# IN-17_tubes.net
KiCad netlist of a schematic drawn in EAGLE
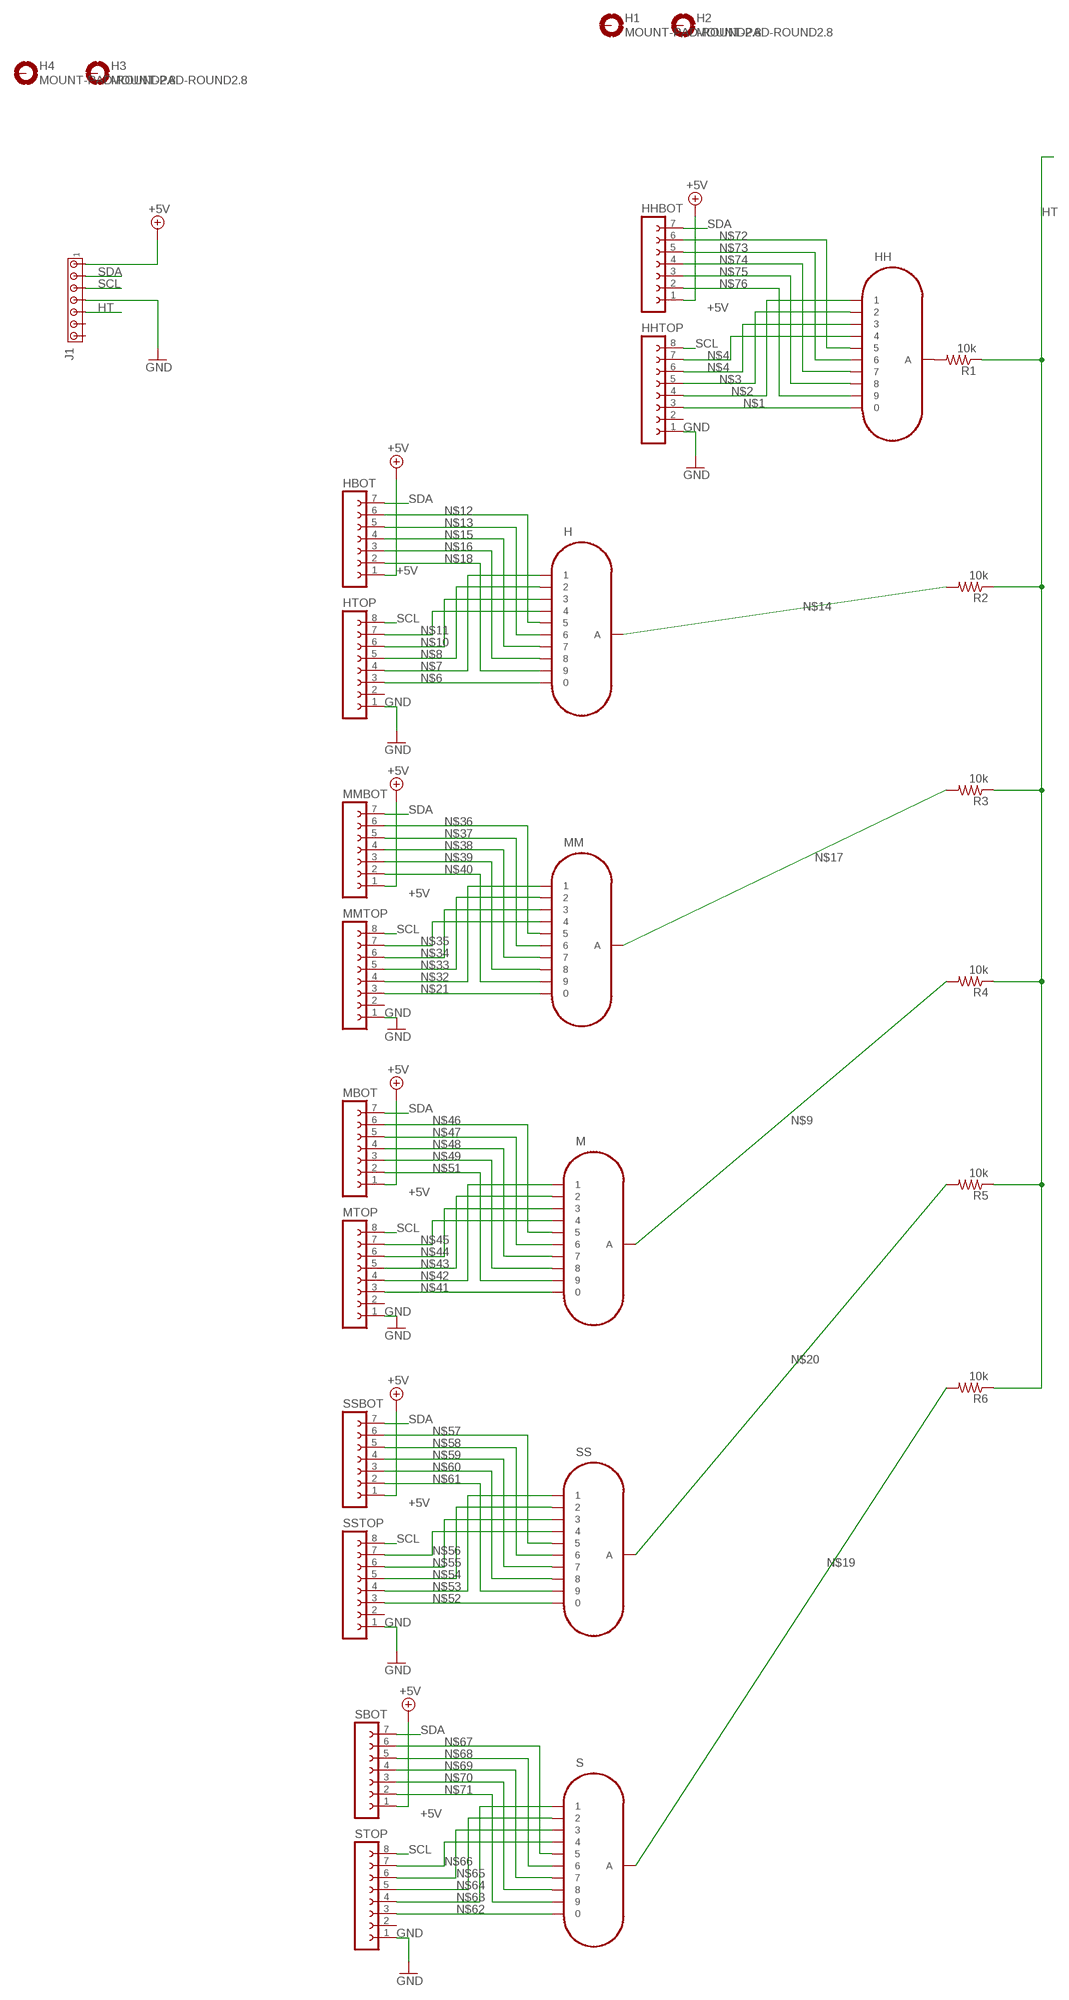
[diagram p0: schematic, sheet 1]

(export (version "E")
  (design (tool "Eeschema 10.0.6"))
  (components
    (comp (ref "H")
      (value "IN-17")
      (footprint "eagle-import:IN-17")
      (libsource (lib "eagle-import") (part "IN-17"))
    )
    (comp (ref "H1")
      (value "MOUNT-PAD-ROUND2.8")
      (footprint "eagle-import:2,8-PAD")
      (libsource (lib "eagle-import") (part "MOUNT-PAD-ROUND2.8"))
    )
    (comp (ref "H2")
      (value "MOUNT-PAD-ROUND2.8")
      (footprint "eagle-import:2,8-PAD")
      (libsource (lib "eagle-import") (part "MOUNT-PAD-ROUND2.8"))
    )
    (comp (ref "H3")
      (value "MOUNT-PAD-ROUND2.8")
      (footprint "eagle-import:2,8-PAD")
      (libsource (lib "eagle-import") (part "MOUNT-PAD-ROUND2.8"))
    )
    (comp (ref "H4")
      (value "MOUNT-PAD-ROUND2.8")
      (footprint "eagle-import:2,8-PAD")
      (libsource (lib "eagle-import") (part "MOUNT-PAD-ROUND2.8"))
    )
    (comp (ref "HBOT")
      (value "FE07-1")
      (footprint "eagle-import:FE07")
      (libsource (lib "eagle-import") (part "FE07-1"))
    )
    (comp (ref "HH")
      (value "IN-17")
      (footprint "eagle-import:IN-17")
      (libsource (lib "eagle-import") (part "IN-17"))
    )
    (comp (ref "HHBOT")
      (value "FE07-1")
      (footprint "eagle-import:FE07")
      (libsource (lib "eagle-import") (part "FE07-1"))
    )
    (comp (ref "HHTOP")
      (value "FE08-1")
      (footprint "eagle-import:FE08")
      (libsource (lib "eagle-import") (part "FE08-1"))
    )
    (comp (ref "HTOP")
      (value "FE08-1")
      (footprint "eagle-import:FE08")
      (libsource (lib "eagle-import") (part "FE08-1"))
    )
    (comp (ref "J1")
      (value "MTA07-100")
      (footprint "eagle-import:10X07MTA")
      (libsource (lib "eagle-import") (part "MTA07-100"))
    )
    (comp (ref "M")
      (value "IN-17")
      (footprint "eagle-import:IN-17")
      (libsource (lib "eagle-import") (part "IN-17"))
    )
    (comp (ref "MBOT")
      (value "FE07-1")
      (footprint "eagle-import:FE07")
      (libsource (lib "eagle-import") (part "FE07-1"))
    )
    (comp (ref "MM")
      (value "IN-17")
      (footprint "eagle-import:IN-17")
      (libsource (lib "eagle-import") (part "IN-17"))
    )
    (comp (ref "MMBOT")
      (value "FE07-1")
      (footprint "eagle-import:FE07")
      (libsource (lib "eagle-import") (part "FE07-1"))
    )
    (comp (ref "MMTOP")
      (value "FE08-1")
      (footprint "eagle-import:FE08")
      (libsource (lib "eagle-import") (part "FE08-1"))
    )
    (comp (ref "MTOP")
      (value "FE08-1")
      (footprint "eagle-import:FE08")
      (libsource (lib "eagle-import") (part "FE08-1"))
    )
    (comp (ref "R1")
      (value "10k")
      (footprint "eagle-import:M0805")
      (libsource (lib "eagle-import") (part "R-US_M0805"))
    )
    (comp (ref "R2")
      (value "10k")
      (footprint "eagle-import:M0805")
      (libsource (lib "eagle-import") (part "R-US_M0805"))
    )
    (comp (ref "R3")
      (value "10k")
      (footprint "eagle-import:M0805")
      (libsource (lib "eagle-import") (part "R-US_M0805"))
    )
    (comp (ref "R4")
      (value "10k")
      (footprint "eagle-import:M0805")
      (libsource (lib "eagle-import") (part "R-US_M0805"))
    )
    (comp (ref "R5")
      (value "10k")
      (footprint "eagle-import:M0805")
      (libsource (lib "eagle-import") (part "R-US_M0805"))
    )
    (comp (ref "R6")
      (value "10k")
      (footprint "eagle-import:M0805")
      (libsource (lib "eagle-import") (part "R-US_M0805"))
    )
    (comp (ref "S")
      (value "IN-17")
      (footprint "eagle-import:IN-17")
      (libsource (lib "eagle-import") (part "IN-17"))
    )
    (comp (ref "SBOT")
      (value "FE07-1")
      (footprint "eagle-import:FE07")
      (libsource (lib "eagle-import") (part "FE07-1"))
    )
    (comp (ref "SS")
      (value "IN-17")
      (footprint "eagle-import:IN-17")
      (libsource (lib "eagle-import") (part "IN-17"))
    )
    (comp (ref "SSBOT")
      (value "FE07-1")
      (footprint "eagle-import:FE07")
      (libsource (lib "eagle-import") (part "FE07-1"))
    )
    (comp (ref "SSTOP")
      (value "FE08-1")
      (footprint "eagle-import:FE08")
      (libsource (lib "eagle-import") (part "FE08-1"))
    )
    (comp (ref "STOP")
      (value "FE08-1")
      (footprint "eagle-import:FE08")
      (libsource (lib "eagle-import") (part "FE08-1"))
    )
  )
  (nets
    (net (code "1") (name "+5V") (class "Default")
      (node (ref "HBOT") (pin "1") (pinfunction "1_1") (pintype "passive"))
      (node (ref "HHBOT") (pin "1") (pinfunction "1_1") (pintype "passive"))
      (node (ref "J1") (pin "1") (pinfunction "1_1") (pintype "passive"))
      (node (ref "MBOT") (pin "1") (pinfunction "1_1") (pintype "passive"))
      (node (ref "MMBOT") (pin "1") (pinfunction "1_1") (pintype "passive"))
      (node (ref "SBOT") (pin "1") (pinfunction "1_1") (pintype "passive"))
      (node (ref "SSBOT") (pin "1") (pinfunction "1_1") (pintype "passive"))
    )
    (net (code "2") (name "/HT") (class "Default")
      (node (ref "J1") (pin "5") (pinfunction "5_5") (pintype "passive"))
      (node (ref "R1") (pin "1") (pinfunction "1_1") (pintype "passive"))
      (node (ref "R2") (pin "1") (pinfunction "1_1") (pintype "passive"))
      (node (ref "R3") (pin "1") (pinfunction "1_1") (pintype "passive"))
      (node (ref "R4") (pin "1") (pinfunction "1_1") (pintype "passive"))
      (node (ref "R5") (pin "1") (pinfunction "1_1") (pintype "passive"))
      (node (ref "R6") (pin "1") (pinfunction "1_1") (pintype "passive"))
    )
    (net (code "3") (name "/N$1") (class "Default")
      (node (ref "HH") (pin "0") (pinfunction "0_0") (pintype "bidirectional"))
      (node (ref "HHTOP") (pin "3") (pinfunction "3_3") (pintype "passive"))
    )
    (net (code "4") (name "/N$2") (class "Default")
      (node (ref "HH") (pin "1") (pinfunction "1_1") (pintype "bidirectional"))
      (node (ref "HHTOP") (pin "4") (pinfunction "4_4") (pintype "passive"))
    )
    (net (code "5") (name "/N$3") (class "Default")
      (node (ref "HH") (pin "2") (pinfunction "2_2") (pintype "bidirectional"))
      (node (ref "HHTOP") (pin "5") (pinfunction "5_5") (pintype "passive"))
    )
    (net (code "6") (name "/N$4") (class "Default")
      (node (ref "HH") (pin "3") (pinfunction "3_3") (pintype "bidirectional"))
      (node (ref "HHTOP") (pin "6") (pinfunction "6_6") (pintype "passive"))
    )
    (net (code "7") (name "/N$6") (class "Default")
      (node (ref "H") (pin "0") (pinfunction "0_0") (pintype "bidirectional"))
      (node (ref "HTOP") (pin "3") (pinfunction "3_3") (pintype "passive"))
    )
    (net (code "8") (name "/N$7") (class "Default")
      (node (ref "H") (pin "1") (pinfunction "1_1") (pintype "bidirectional"))
      (node (ref "HTOP") (pin "4") (pinfunction "4_4") (pintype "passive"))
    )
    (net (code "9") (name "/N$8") (class "Default")
      (node (ref "H") (pin "2") (pinfunction "2_2") (pintype "bidirectional"))
      (node (ref "HTOP") (pin "5") (pinfunction "5_5") (pintype "passive"))
    )
    (net (code "10") (name "/N$9") (class "Default")
      (node (ref "M") (pin "A") (pinfunction "A_A") (pintype "bidirectional"))
      (node (ref "R4") (pin "2") (pinfunction "2_2") (pintype "passive"))
    )
    (net (code "11") (name "/N$10") (class "Default")
      (node (ref "H") (pin "3") (pinfunction "3_3") (pintype "bidirectional"))
      (node (ref "HTOP") (pin "6") (pinfunction "6_6") (pintype "passive"))
    )
    (net (code "12") (name "/N$11") (class "Default")
      (node (ref "H") (pin "4") (pinfunction "4_4") (pintype "bidirectional"))
      (node (ref "HTOP") (pin "7") (pinfunction "7_7") (pintype "passive"))
    )
    (net (code "13") (name "/N$12") (class "Default")
      (node (ref "H") (pin "5") (pinfunction "5_5") (pintype "bidirectional"))
      (node (ref "HBOT") (pin "6") (pinfunction "6_6") (pintype "passive"))
    )
    (net (code "14") (name "/N$13") (class "Default")
      (node (ref "H") (pin "6") (pinfunction "6_6") (pintype "bidirectional"))
      (node (ref "HBOT") (pin "5") (pinfunction "5_5") (pintype "passive"))
    )
    (net (code "15") (name "/N$14") (class "Default")
      (node (ref "H") (pin "A") (pinfunction "A_A") (pintype "bidirectional"))
      (node (ref "R2") (pin "2") (pinfunction "2_2") (pintype "passive"))
    )
    (net (code "16") (name "/N$15") (class "Default")
      (node (ref "H") (pin "7") (pinfunction "7_7") (pintype "bidirectional"))
      (node (ref "HBOT") (pin "4") (pinfunction "4_4") (pintype "passive"))
    )
    (net (code "17") (name "/N$16") (class "Default")
      (node (ref "H") (pin "8") (pinfunction "8_8") (pintype "bidirectional"))
      (node (ref "HBOT") (pin "3") (pinfunction "3_3") (pintype "passive"))
    )
    (net (code "18") (name "/N$17") (class "Default")
      (node (ref "MM") (pin "A") (pinfunction "A_A") (pintype "bidirectional"))
      (node (ref "R3") (pin "2") (pinfunction "2_2") (pintype "passive"))
    )
    (net (code "19") (name "/N$18") (class "Default")
      (node (ref "H") (pin "9") (pinfunction "9_9") (pintype "bidirectional"))
      (node (ref "HBOT") (pin "2") (pinfunction "2_2") (pintype "passive"))
    )
    (net (code "20") (name "/N$19") (class "Default")
      (node (ref "R6") (pin "2") (pinfunction "2_2") (pintype "passive"))
      (node (ref "S") (pin "A") (pinfunction "A_A") (pintype "bidirectional"))
    )
    (net (code "21") (name "/N$20") (class "Default")
      (node (ref "R5") (pin "2") (pinfunction "2_2") (pintype "passive"))
      (node (ref "SS") (pin "A") (pinfunction "A_A") (pintype "bidirectional"))
    )
    (net (code "22") (name "/N$21") (class "Default")
      (node (ref "MM") (pin "0") (pinfunction "0_0") (pintype "bidirectional"))
      (node (ref "MMTOP") (pin "3") (pinfunction "3_3") (pintype "passive"))
    )
    (net (code "23") (name "/N$32") (class "Default")
      (node (ref "MM") (pin "1") (pinfunction "1_1") (pintype "bidirectional"))
      (node (ref "MMTOP") (pin "4") (pinfunction "4_4") (pintype "passive"))
    )
    (net (code "24") (name "/N$33") (class "Default")
      (node (ref "MM") (pin "2") (pinfunction "2_2") (pintype "bidirectional"))
      (node (ref "MMTOP") (pin "5") (pinfunction "5_5") (pintype "passive"))
    )
    (net (code "25") (name "/N$34") (class "Default")
      (node (ref "MM") (pin "3") (pinfunction "3_3") (pintype "bidirectional"))
      (node (ref "MMTOP") (pin "6") (pinfunction "6_6") (pintype "passive"))
    )
    (net (code "26") (name "/N$35") (class "Default")
      (node (ref "MM") (pin "4") (pinfunction "4_4") (pintype "bidirectional"))
      (node (ref "MMTOP") (pin "7") (pinfunction "7_7") (pintype "passive"))
    )
    (net (code "27") (name "/N$36") (class "Default")
      (node (ref "MM") (pin "5") (pinfunction "5_5") (pintype "bidirectional"))
      (node (ref "MMBOT") (pin "6") (pinfunction "6_6") (pintype "passive"))
    )
    (net (code "28") (name "/N$37") (class "Default")
      (node (ref "MM") (pin "6") (pinfunction "6_6") (pintype "bidirectional"))
      (node (ref "MMBOT") (pin "5") (pinfunction "5_5") (pintype "passive"))
    )
    (net (code "29") (name "/N$38") (class "Default")
      (node (ref "MM") (pin "7") (pinfunction "7_7") (pintype "bidirectional"))
      (node (ref "MMBOT") (pin "4") (pinfunction "4_4") (pintype "passive"))
    )
    (net (code "30") (name "/N$39") (class "Default")
      (node (ref "MM") (pin "8") (pinfunction "8_8") (pintype "bidirectional"))
      (node (ref "MMBOT") (pin "3") (pinfunction "3_3") (pintype "passive"))
    )
    (net (code "31") (name "/N$40") (class "Default")
      (node (ref "MM") (pin "9") (pinfunction "9_9") (pintype "bidirectional"))
      (node (ref "MMBOT") (pin "2") (pinfunction "2_2") (pintype "passive"))
    )
    (net (code "32") (name "/N$41") (class "Default")
      (node (ref "M") (pin "0") (pinfunction "0_0") (pintype "bidirectional"))
      (node (ref "MTOP") (pin "3") (pinfunction "3_3") (pintype "passive"))
    )
    (net (code "33") (name "/N$42") (class "Default")
      (node (ref "M") (pin "1") (pinfunction "1_1") (pintype "bidirectional"))
      (node (ref "MTOP") (pin "4") (pinfunction "4_4") (pintype "passive"))
    )
    (net (code "34") (name "/N$43") (class "Default")
      (node (ref "M") (pin "2") (pinfunction "2_2") (pintype "bidirectional"))
      (node (ref "MTOP") (pin "5") (pinfunction "5_5") (pintype "passive"))
    )
    (net (code "35") (name "/N$44") (class "Default")
      (node (ref "M") (pin "3") (pinfunction "3_3") (pintype "bidirectional"))
      (node (ref "MTOP") (pin "6") (pinfunction "6_6") (pintype "passive"))
    )
    (net (code "36") (name "/N$45") (class "Default")
      (node (ref "M") (pin "4") (pinfunction "4_4") (pintype "bidirectional"))
      (node (ref "MTOP") (pin "7") (pinfunction "7_7") (pintype "passive"))
    )
    (net (code "37") (name "/N$46") (class "Default")
      (node (ref "M") (pin "5") (pinfunction "5_5") (pintype "bidirectional"))
      (node (ref "MBOT") (pin "6") (pinfunction "6_6") (pintype "passive"))
    )
    (net (code "38") (name "/N$47") (class "Default")
      (node (ref "M") (pin "6") (pinfunction "6_6") (pintype "bidirectional"))
      (node (ref "MBOT") (pin "5") (pinfunction "5_5") (pintype "passive"))
    )
    (net (code "39") (name "/N$48") (class "Default")
      (node (ref "M") (pin "7") (pinfunction "7_7") (pintype "bidirectional"))
      (node (ref "MBOT") (pin "4") (pinfunction "4_4") (pintype "passive"))
    )
    (net (code "40") (name "/N$49") (class "Default")
      (node (ref "M") (pin "8") (pinfunction "8_8") (pintype "bidirectional"))
      (node (ref "MBOT") (pin "3") (pinfunction "3_3") (pintype "passive"))
    )
    (net (code "41") (name "/N$51") (class "Default")
      (node (ref "M") (pin "9") (pinfunction "9_9") (pintype "bidirectional"))
      (node (ref "MBOT") (pin "2") (pinfunction "2_2") (pintype "passive"))
    )
    (net (code "42") (name "/N$52") (class "Default")
      (node (ref "SS") (pin "0") (pinfunction "0_0") (pintype "bidirectional"))
      (node (ref "SSTOP") (pin "3") (pinfunction "3_3") (pintype "passive"))
    )
    (net (code "43") (name "/N$53") (class "Default")
      (node (ref "SS") (pin "1") (pinfunction "1_1") (pintype "bidirectional"))
      (node (ref "SSTOP") (pin "4") (pinfunction "4_4") (pintype "passive"))
    )
    (net (code "44") (name "/N$54") (class "Default")
      (node (ref "SS") (pin "2") (pinfunction "2_2") (pintype "bidirectional"))
      (node (ref "SSTOP") (pin "5") (pinfunction "5_5") (pintype "passive"))
    )
    (net (code "45") (name "/N$55") (class "Default")
      (node (ref "SS") (pin "3") (pinfunction "3_3") (pintype "bidirectional"))
      (node (ref "SSTOP") (pin "6") (pinfunction "6_6") (pintype "passive"))
    )
    (net (code "46") (name "/N$56") (class "Default")
      (node (ref "SS") (pin "4") (pinfunction "4_4") (pintype "bidirectional"))
      (node (ref "SSTOP") (pin "7") (pinfunction "7_7") (pintype "passive"))
    )
    (net (code "47") (name "/N$57") (class "Default")
      (node (ref "SS") (pin "5") (pinfunction "5_5") (pintype "bidirectional"))
      (node (ref "SSBOT") (pin "6") (pinfunction "6_6") (pintype "passive"))
    )
    (net (code "48") (name "/N$58") (class "Default")
      (node (ref "SS") (pin "6") (pinfunction "6_6") (pintype "bidirectional"))
      (node (ref "SSBOT") (pin "5") (pinfunction "5_5") (pintype "passive"))
    )
    (net (code "49") (name "/N$59") (class "Default")
      (node (ref "SS") (pin "7") (pinfunction "7_7") (pintype "bidirectional"))
      (node (ref "SSBOT") (pin "4") (pinfunction "4_4") (pintype "passive"))
    )
    (net (code "50") (name "/N$60") (class "Default")
      (node (ref "SS") (pin "8") (pinfunction "8_8") (pintype "bidirectional"))
      (node (ref "SSBOT") (pin "3") (pinfunction "3_3") (pintype "passive"))
    )
    (net (code "51") (name "/N$61") (class "Default")
      (node (ref "SS") (pin "9") (pinfunction "9_9") (pintype "bidirectional"))
      (node (ref "SSBOT") (pin "2") (pinfunction "2_2") (pintype "passive"))
    )
    (net (code "52") (name "/N$62") (class "Default")
      (node (ref "S") (pin "0") (pinfunction "0_0") (pintype "bidirectional"))
      (node (ref "STOP") (pin "3") (pinfunction "3_3") (pintype "passive"))
    )
    (net (code "53") (name "/N$63") (class "Default")
      (node (ref "S") (pin "1") (pinfunction "1_1") (pintype "bidirectional"))
      (node (ref "STOP") (pin "4") (pinfunction "4_4") (pintype "passive"))
    )
    (net (code "54") (name "/N$64") (class "Default")
      (node (ref "S") (pin "2") (pinfunction "2_2") (pintype "bidirectional"))
      (node (ref "STOP") (pin "5") (pinfunction "5_5") (pintype "passive"))
    )
    (net (code "55") (name "/N$65") (class "Default")
      (node (ref "S") (pin "3") (pinfunction "3_3") (pintype "bidirectional"))
      (node (ref "STOP") (pin "6") (pinfunction "6_6") (pintype "passive"))
    )
    (net (code "56") (name "/N$66") (class "Default")
      (node (ref "S") (pin "4") (pinfunction "4_4") (pintype "bidirectional"))
      (node (ref "STOP") (pin "7") (pinfunction "7_7") (pintype "passive"))
    )
    (net (code "57") (name "/N$67") (class "Default")
      (node (ref "S") (pin "5") (pinfunction "5_5") (pintype "bidirectional"))
      (node (ref "SBOT") (pin "6") (pinfunction "6_6") (pintype "passive"))
    )
    (net (code "58") (name "/N$68") (class "Default")
      (node (ref "S") (pin "6") (pinfunction "6_6") (pintype "bidirectional"))
      (node (ref "SBOT") (pin "5") (pinfunction "5_5") (pintype "passive"))
    )
    (net (code "59") (name "/N$69") (class "Default")
      (node (ref "S") (pin "7") (pinfunction "7_7") (pintype "bidirectional"))
      (node (ref "SBOT") (pin "4") (pinfunction "4_4") (pintype "passive"))
    )
    (net (code "60") (name "/N$70") (class "Default")
      (node (ref "S") (pin "8") (pinfunction "8_8") (pintype "bidirectional"))
      (node (ref "SBOT") (pin "3") (pinfunction "3_3") (pintype "passive"))
    )
    (net (code "61") (name "/N$71") (class "Default")
      (node (ref "S") (pin "9") (pinfunction "9_9") (pintype "bidirectional"))
      (node (ref "SBOT") (pin "2") (pinfunction "2_2") (pintype "passive"))
    )
    (net (code "62") (name "/N$72") (class "Default")
      (node (ref "HH") (pin "5") (pinfunction "5_5") (pintype "bidirectional"))
      (node (ref "HHBOT") (pin "6") (pinfunction "6_6") (pintype "passive"))
    )
    (net (code "63") (name "/N$73") (class "Default")
      (node (ref "HH") (pin "6") (pinfunction "6_6") (pintype "bidirectional"))
      (node (ref "HHBOT") (pin "5") (pinfunction "5_5") (pintype "passive"))
    )
    (net (code "64") (name "/N$74") (class "Default")
      (node (ref "HH") (pin "7") (pinfunction "7_7") (pintype "bidirectional"))
      (node (ref "HHBOT") (pin "4") (pinfunction "4_4") (pintype "passive"))
    )
    (net (code "65") (name "/N$75") (class "Default")
      (node (ref "HH") (pin "8") (pinfunction "8_8") (pintype "bidirectional"))
      (node (ref "HHBOT") (pin "3") (pinfunction "3_3") (pintype "passive"))
    )
    (net (code "66") (name "/N$76") (class "Default")
      (node (ref "HH") (pin "9") (pinfunction "9_9") (pintype "bidirectional"))
      (node (ref "HHBOT") (pin "2") (pinfunction "2_2") (pintype "passive"))
    )
    (net (code "67") (name "/SCL") (class "Default")
      (node (ref "HHTOP") (pin "8") (pinfunction "8_8") (pintype "passive"))
      (node (ref "HTOP") (pin "8") (pinfunction "8_8") (pintype "passive"))
      (node (ref "J1") (pin "3") (pinfunction "3_3") (pintype "passive"))
      (node (ref "MMTOP") (pin "8") (pinfunction "8_8") (pintype "passive"))
      (node (ref "MTOP") (pin "8") (pinfunction "8_8") (pintype "passive"))
      (node (ref "SSTOP") (pin "8") (pinfunction "8_8") (pintype "passive"))
      (node (ref "STOP") (pin "8") (pinfunction "8_8") (pintype "passive"))
    )
    (net (code "68") (name "/SDA") (class "Default")
      (node (ref "HBOT") (pin "7") (pinfunction "7_7") (pintype "passive"))
      (node (ref "HHBOT") (pin "7") (pinfunction "7_7") (pintype "passive"))
      (node (ref "J1") (pin "2") (pinfunction "2_2") (pintype "passive"))
      (node (ref "MBOT") (pin "7") (pinfunction "7_7") (pintype "passive"))
      (node (ref "MMBOT") (pin "7") (pinfunction "7_7") (pintype "passive"))
      (node (ref "SBOT") (pin "7") (pinfunction "7_7") (pintype "passive"))
      (node (ref "SSBOT") (pin "7") (pinfunction "7_7") (pintype "passive"))
    )
    (net (code "69") (name "GND") (class "Default")
      (node (ref "HHTOP") (pin "1") (pinfunction "1_1") (pintype "passive"))
      (node (ref "HTOP") (pin "1") (pinfunction "1_1") (pintype "passive"))
      (node (ref "J1") (pin "4") (pinfunction "4_4") (pintype "passive"))
      (node (ref "MMTOP") (pin "1") (pinfunction "1_1") (pintype "passive"))
      (node (ref "MTOP") (pin "1") (pinfunction "1_1") (pintype "passive"))
      (node (ref "SSTOP") (pin "1") (pinfunction "1_1") (pintype "passive"))
      (node (ref "STOP") (pin "1") (pinfunction "1_1") (pintype "passive"))
    )
    (net (code "70") (name "Net-(HH-Pad4)") (class "Default")
      (node (ref "HH") (pin "4") (pinfunction "4_4") (pintype "bidirectional"))
      (node (ref "HHTOP") (pin "7") (pinfunction "7_7") (pintype "passive"))
    )
    (net (code "71") (name "Net-(HH-PadA)") (class "Default")
      (node (ref "HH") (pin "A") (pinfunction "A_A") (pintype "bidirectional"))
      (node (ref "R1") (pin "2") (pinfunction "2_2") (pintype "passive"))
    )
    (net (code "72") (name "unconnected-(H1-MOUNT-PadB2,8)") (class "Default")
      (node (ref "H1") (pin "B2,8") (pinfunction "MOUNT_B2,8") (pintype "passive"))
    )
    (net (code "73") (name "unconnected-(H2-MOUNT-PadB2,8)") (class "Default")
      (node (ref "H2") (pin "B2,8") (pinfunction "MOUNT_B2,8") (pintype "passive"))
    )
    (net (code "74") (name "unconnected-(H3-MOUNT-PadB2,8)") (class "Default")
      (node (ref "H3") (pin "B2,8") (pinfunction "MOUNT_B2,8") (pintype "passive"))
    )
    (net (code "75") (name "unconnected-(H4-MOUNT-PadB2,8)") (class "Default")
      (node (ref "H4") (pin "B2,8") (pinfunction "MOUNT_B2,8") (pintype "passive"))
    )
    (net (code "76") (name "unconnected-(HHTOP-Pad2)") (class "Default")
      (node (ref "HHTOP") (pin "2") (pinfunction "2_2") (pintype "passive"))
    )
    (net (code "77") (name "unconnected-(HTOP-Pad2)") (class "Default")
      (node (ref "HTOP") (pin "2") (pinfunction "2_2") (pintype "passive"))
    )
    (net (code "78") (name "unconnected-(J1-Pad6)") (class "Default")
      (node (ref "J1") (pin "6") (pinfunction "6_6") (pintype "passive"))
    )
    (net (code "79") (name "unconnected-(J1-Pad7)") (class "Default")
      (node (ref "J1") (pin "7") (pinfunction "7_7") (pintype "passive"))
    )
    (net (code "80") (name "unconnected-(MMTOP-Pad2)") (class "Default")
      (node (ref "MMTOP") (pin "2") (pinfunction "2_2") (pintype "passive"))
    )
    (net (code "81") (name "unconnected-(MTOP-Pad2)") (class "Default")
      (node (ref "MTOP") (pin "2") (pinfunction "2_2") (pintype "passive"))
    )
    (net (code "82") (name "unconnected-(SSTOP-Pad2)") (class "Default")
      (node (ref "SSTOP") (pin "2") (pinfunction "2_2") (pintype "passive"))
    )
    (net (code "83") (name "unconnected-(STOP-Pad2)") (class "Default")
      (node (ref "STOP") (pin "2") (pinfunction "2_2") (pintype "passive"))
    )
  )
)
